# USB-CAN-Adapter.net
KiCad netlist of a schematic drawn in EAGLE
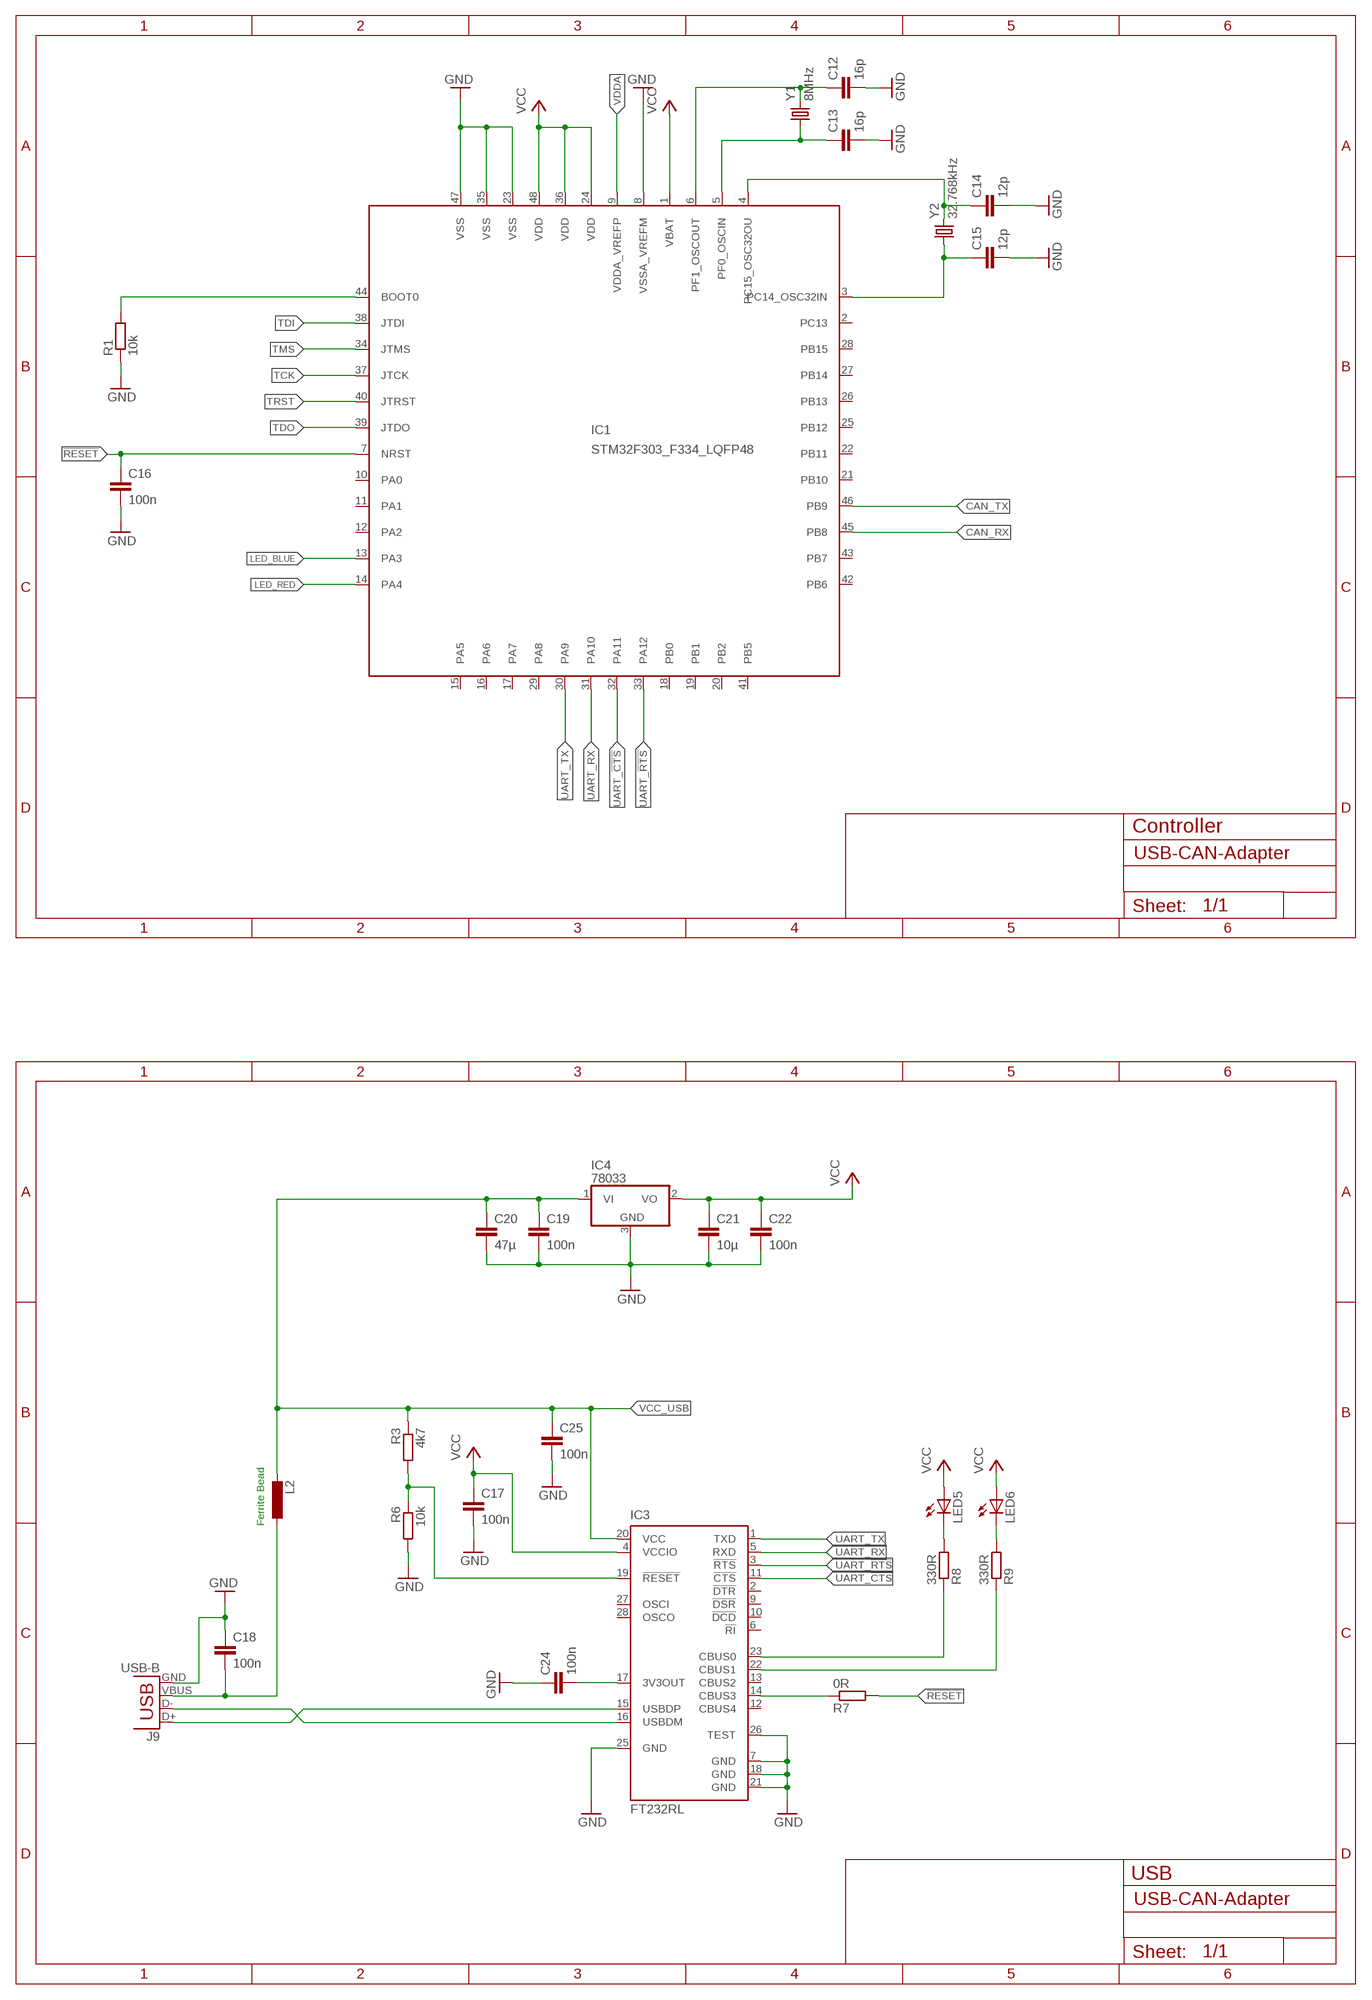
[diagram p0: schematic, sheet 1, part 1 of 2]
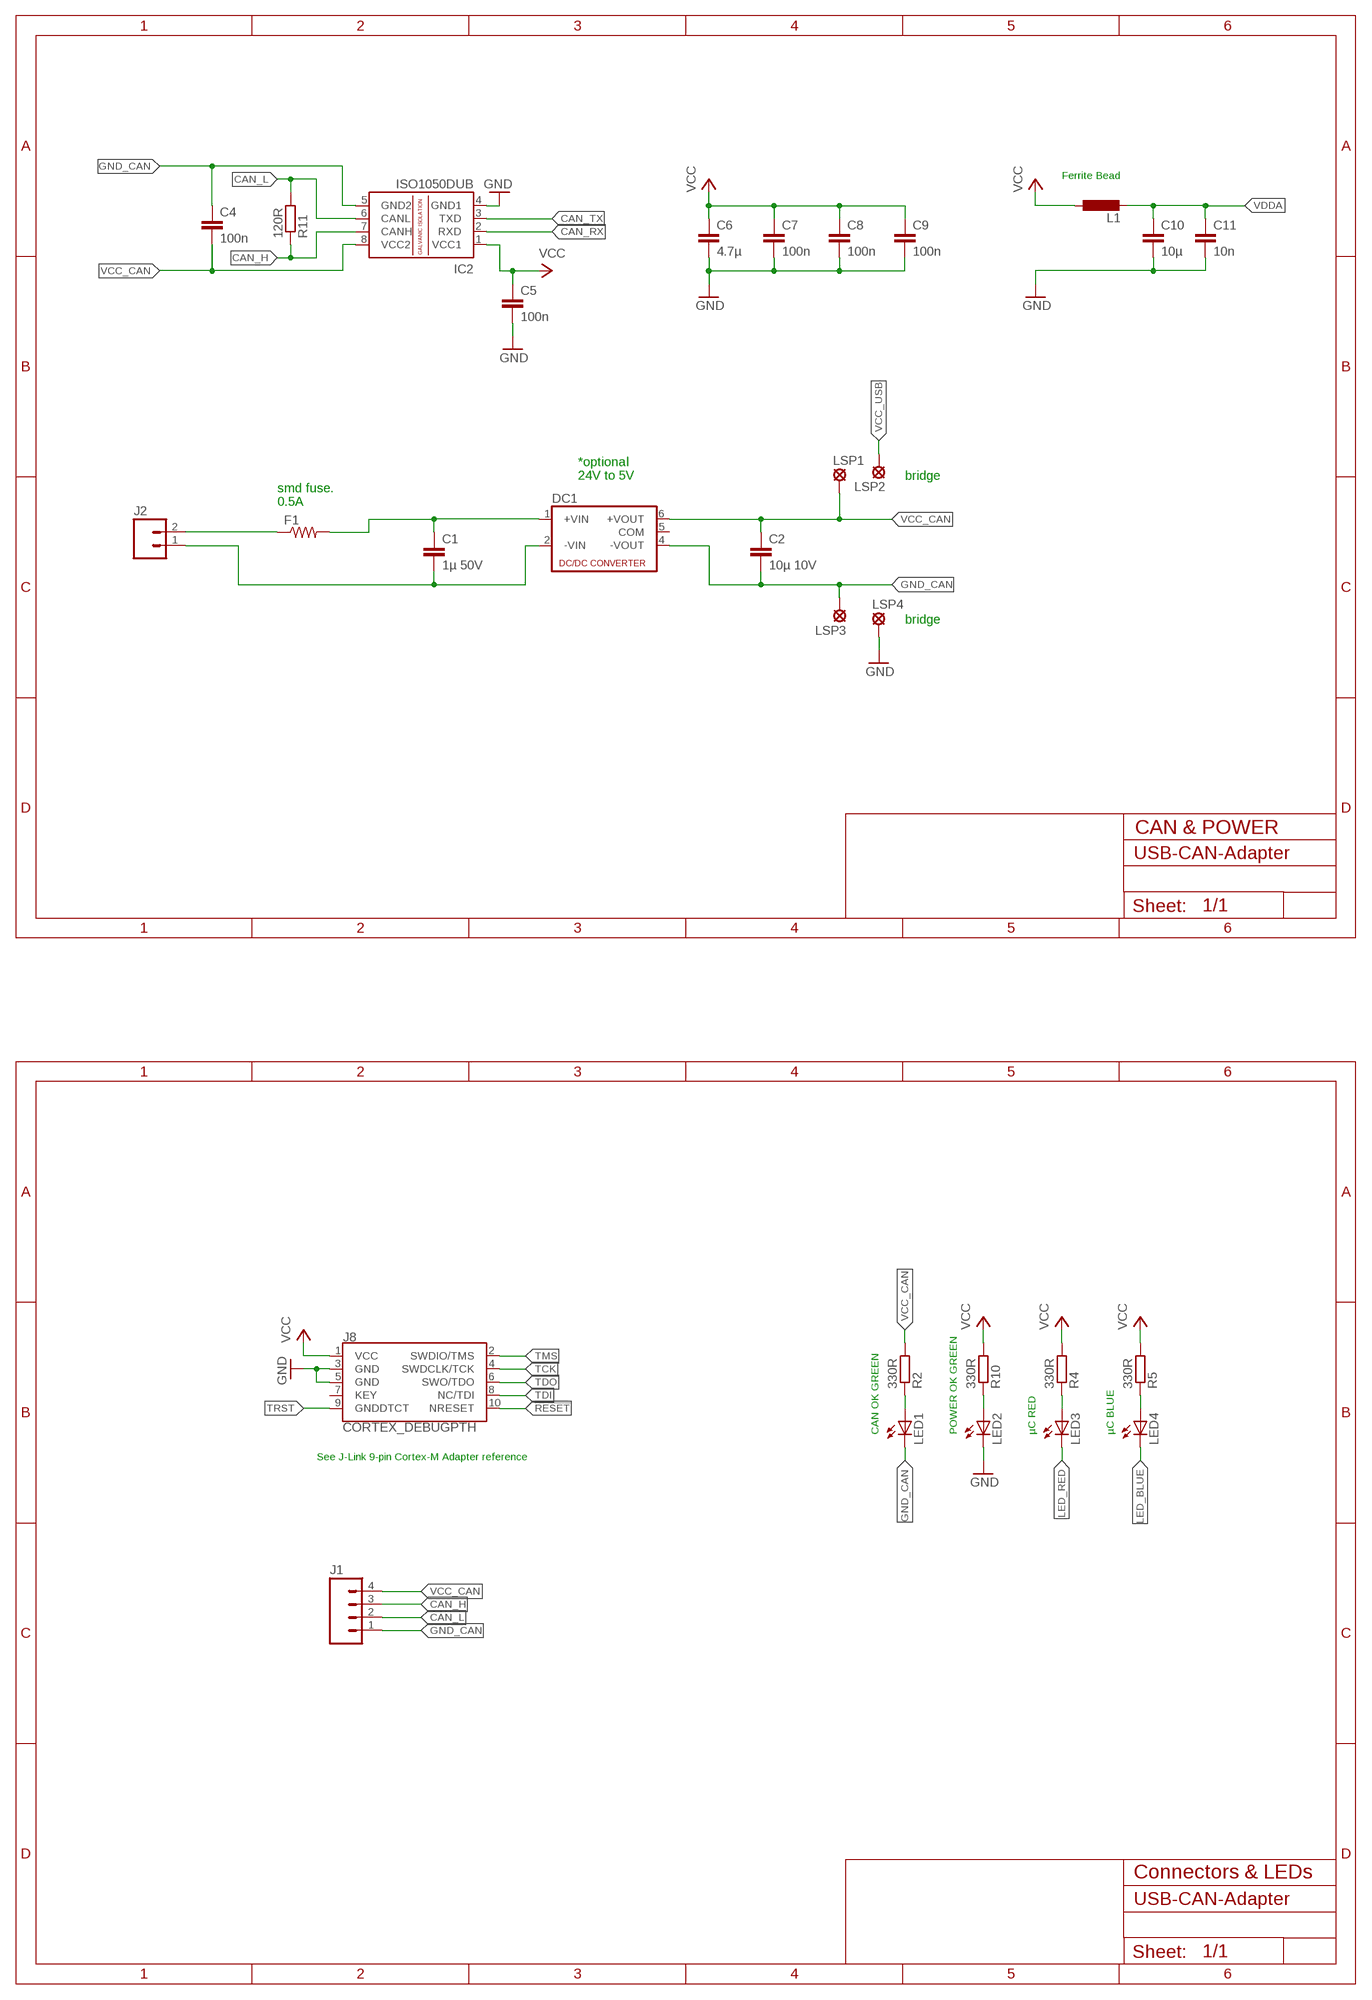
[diagram p1: schematic, sheet 1, part 2 of 2]

(export (version "E")
  (design (tool "Eeschema 10.0.6"))
  (components
    (comp (ref "C1")
      (value "1µ 50V")
      (footprint "eagle-import:C0805")
      (libsource (lib "eagle-import") (part "C-EUC0805"))
    )
    (comp (ref "C2")
      (value "10µ 10V")
      (footprint "eagle-import:C0805")
      (libsource (lib "eagle-import") (part "C-EUC0805"))
    )
    (comp (ref "C4")
      (value "100n")
      (footprint "eagle-import:C0805")
      (libsource (lib "eagle-import") (part "C-EUC0805"))
    )
    (comp (ref "C5")
      (value "100n")
      (footprint "eagle-import:C0805")
      (libsource (lib "eagle-import") (part "C-EUC0805"))
    )
    (comp (ref "C6")
      (value "4.7µ")
      (footprint "eagle-import:C0805")
      (libsource (lib "eagle-import") (part "C-EUC0805"))
    )
    (comp (ref "C7")
      (value "100n")
      (footprint "eagle-import:C0805")
      (libsource (lib "eagle-import") (part "C-EUC0805"))
    )
    (comp (ref "C8")
      (value "100n")
      (footprint "eagle-import:C0805")
      (libsource (lib "eagle-import") (part "C-EUC0805"))
    )
    (comp (ref "C9")
      (value "100n")
      (footprint "eagle-import:C0805")
      (libsource (lib "eagle-import") (part "C-EUC0805"))
    )
    (comp (ref "C10")
      (value "10µ")
      (footprint "eagle-import:C0805")
      (libsource (lib "eagle-import") (part "C-EUC0805"))
    )
    (comp (ref "C11")
      (value "10n")
      (footprint "eagle-import:C0805")
      (libsource (lib "eagle-import") (part "C-EUC0805"))
    )
    (comp (ref "C12")
      (value "16p")
      (footprint "eagle-import:C0805")
      (libsource (lib "eagle-import") (part "C-EUC0805"))
    )
    (comp (ref "C13")
      (value "16p")
      (footprint "eagle-import:C0805")
      (libsource (lib "eagle-import") (part "C-EUC0805"))
    )
    (comp (ref "C14")
      (value "12p")
      (footprint "eagle-import:C0805")
      (libsource (lib "eagle-import") (part "C-EUC0805"))
    )
    (comp (ref "C15")
      (value "12p")
      (footprint "eagle-import:C0805")
      (libsource (lib "eagle-import") (part "C-EUC0805"))
    )
    (comp (ref "C16")
      (value "100n")
      (footprint "eagle-import:C0805")
      (libsource (lib "eagle-import") (part "C-EUC0805"))
    )
    (comp (ref "C17")
      (value "100n")
      (footprint "eagle-import:C0805")
      (libsource (lib "eagle-import") (part "C-EUC0805"))
    )
    (comp (ref "C18")
      (value "100n")
      (footprint "eagle-import:C0805")
      (libsource (lib "eagle-import") (part "C-EUC0805"))
    )
    (comp (ref "C19")
      (value "100n")
      (footprint "eagle-import:C0805")
      (libsource (lib "eagle-import") (part "C-EUC0805"))
    )
    (comp (ref "C20")
      (value "47µ")
      (footprint "eagle-import:C0805")
      (libsource (lib "eagle-import") (part "C-EUC0805"))
    )
    (comp (ref "C21")
      (value "10µ")
      (footprint "eagle-import:C0805")
      (libsource (lib "eagle-import") (part "C-EUC0805"))
    )
    (comp (ref "C22")
      (value "100n")
      (footprint "eagle-import:C0805")
      (libsource (lib "eagle-import") (part "C-EUC0805"))
    )
    (comp (ref "C24")
      (value "100n")
      (footprint "eagle-import:C0805")
      (libsource (lib "eagle-import") (part "C-EUC0805"))
    )
    (comp (ref "C25")
      (value "100n")
      (footprint "eagle-import:C0805")
      (libsource (lib "eagle-import") (part "C-EUC0805"))
    )
    (comp (ref "DC1")
      (value "NMA")
      (footprint "eagle-import:NMA")
      (fields (field (name "MF") "C & D TECHNOLOGIES, INC") (field (name "MPN") "NMA0515SC"))
      (libsource (lib "eagle-import") (part "NMA"))
    )
    (comp (ref "F1")
      (value "R-US_R0805")
      (footprint "eagle-import:R0805")
      (libsource (lib "eagle-import") (part "R-US_R0805"))
    )
    (comp (ref "IC1")
      (value "STM32F303_F334_LQFP48")
      (footprint "eagle-import:LQFP48_PACKAGE")
      (libsource (lib "eagle-import") (part "STM32F303_F334_LQFP48"))
    )
    (comp (ref "IC2")
      (value "ISO1050DUB")
      (footprint "eagle-import:DUB-R-PDSO-G8")
      (fields (field (name "MPN") "ISO1050DUBR"))
      (libsource (lib "eagle-import") (part "ISO1050DUB"))
    )
    (comp (ref "IC3")
      (value "FT232RL")
      (footprint "eagle-import:SSOP28")
      (libsource (lib "eagle-import") (part "FT232RL"))
    )
    (comp (ref "IC4")
      (value "78033")
      (footprint "eagle-import:TO252")
      (libsource (lib "eagle-import") (part "78DT05"))
    )
    (comp (ref "J1")
      (value "M04SCREW")
      (footprint "eagle-import:SCREWTERMINAL-3.5MM-4")
      (libsource (lib "eagle-import") (part "M04SCREW"))
    )
    (comp (ref "J2")
      (value "M023.5MM")
      (footprint "eagle-import:SCREWTERMINAL-3.5MM-2")
      (libsource (lib "eagle-import") (part "M023.5MM"))
    )
    (comp (ref "J8")
      (value "CORTEX_DEBUGPTH")
      (footprint "eagle-import:2X5-PTH-1.27MM")
      (libsource (lib "eagle-import") (part "CORTEX_DEBUGPTH"))
    )
    (comp (ref "J9")
      (value "USB-B")
      (footprint "eagle-import:USB-B-PTH")
      (libsource (lib "eagle-import") (part "USBPTH"))
    )
    (comp (ref "L1")
      (value "L-EUL2012C")
      (footprint "eagle-import:L2012C")
      (libsource (lib "eagle-import") (part "L-EUL2012C"))
    )
    (comp (ref "L2")
      (value "L-EUL2012C")
      (footprint "eagle-import:L2012C")
      (libsource (lib "eagle-import") (part "L-EUL2012C"))
    )
    (comp (ref "LED1")
      (value "LEDCHIP-LED0805")
      (footprint "eagle-import:CHIP-LED0805")
      (libsource (lib "eagle-import") (part "LEDCHIP-LED0805"))
    )
    (comp (ref "LED2")
      (value "LEDCHIP-LED0805")
      (footprint "eagle-import:CHIP-LED0805")
      (libsource (lib "eagle-import") (part "LEDCHIP-LED0805"))
    )
    (comp (ref "LED3")
      (value "LEDCHIP-LED0805")
      (footprint "eagle-import:CHIP-LED0805")
      (libsource (lib "eagle-import") (part "LEDCHIP-LED0805"))
    )
    (comp (ref "LED4")
      (value "LEDCHIP-LED0805")
      (footprint "eagle-import:CHIP-LED0805")
      (libsource (lib "eagle-import") (part "LEDCHIP-LED0805"))
    )
    (comp (ref "LED5")
      (value "LEDCHIP-LED0805")
      (footprint "eagle-import:CHIP-LED0805")
      (libsource (lib "eagle-import") (part "LEDCHIP-LED0805"))
    )
    (comp (ref "LED6")
      (value "LEDCHIP-LED0805")
      (footprint "eagle-import:CHIP-LED0805")
      (libsource (lib "eagle-import") (part "LEDCHIP-LED0805"))
    )
    (comp (ref "LSP1")
      (value "LSP13")
      (footprint "eagle-import:LSP13")
      (libsource (lib "eagle-import") (part "LSP13"))
    )
    (comp (ref "LSP2")
      (value "LSP13")
      (footprint "eagle-import:LSP13")
      (libsource (lib "eagle-import") (part "LSP13"))
    )
    (comp (ref "LSP3")
      (value "LSP13")
      (footprint "eagle-import:LSP13")
      (libsource (lib "eagle-import") (part "LSP13"))
    )
    (comp (ref "LSP4")
      (value "LSP13")
      (footprint "eagle-import:LSP13")
      (libsource (lib "eagle-import") (part "LSP13"))
    )
    (comp (ref "R1")
      (value "10k")
      (footprint "eagle-import:R0805")
      (libsource (lib "eagle-import") (part "R-EU_R0805"))
    )
    (comp (ref "R2")
      (value "330R")
      (footprint "eagle-import:R0805")
      (libsource (lib "eagle-import") (part "R-EU_R0805"))
    )
    (comp (ref "R3")
      (value "4k7")
      (footprint "eagle-import:R0805")
      (libsource (lib "eagle-import") (part "R-EU_R0805"))
    )
    (comp (ref "R4")
      (value "330R")
      (footprint "eagle-import:R0805")
      (libsource (lib "eagle-import") (part "R-EU_R0805"))
    )
    (comp (ref "R5")
      (value "330R")
      (footprint "eagle-import:R0805")
      (libsource (lib "eagle-import") (part "R-EU_R0805"))
    )
    (comp (ref "R6")
      (value "10k")
      (footprint "eagle-import:R0805")
      (libsource (lib "eagle-import") (part "R-EU_R0805"))
    )
    (comp (ref "R7")
      (value "0R")
      (footprint "eagle-import:R0805")
      (libsource (lib "eagle-import") (part "R-EU_R0805"))
    )
    (comp (ref "R8")
      (value "330R")
      (footprint "eagle-import:R0805")
      (libsource (lib "eagle-import") (part "R-EU_R0805"))
    )
    (comp (ref "R9")
      (value "330R")
      (footprint "eagle-import:R0805")
      (libsource (lib "eagle-import") (part "R-EU_R0805"))
    )
    (comp (ref "R10")
      (value "330R")
      (footprint "eagle-import:R0805")
      (libsource (lib "eagle-import") (part "R-EU_R0805"))
    )
    (comp (ref "R11")
      (value "120R")
      (footprint "eagle-import:R0805")
      (libsource (lib "eagle-import") (part "R-EU_R0805"))
    )
    (comp (ref "Y1")
      (value "8MHz")
      (footprint "eagle-import:CRYSTAL-SMD-5X3")
      (libsource (lib "eagle-import") (part "CRYSTALCRYSTAL-SMD-5X3-12.288MHZ"))
    )
    (comp (ref "Y2")
      (value "32.768kHz")
      (footprint "eagle-import:CRYSTAL-SMD-3.2X1.5MM")
      (libsource (lib "eagle-import") (part "CRYSTAL3.2X1.5MM"))
    )
  )
  (nets
    (net (code "1") (name "/UART_~{CTS}") (class "Default")
      (node (ref "IC1") (pin "32") (pinfunction "PA11_32") (pintype "bidirectional"))
      (node (ref "IC3") (pin "11") (pinfunction "~{CTS}_11") (pintype "input"))
    )
    (net (code "2") (name "/UART_~{RTS}") (class "Default")
      (node (ref "IC1") (pin "33") (pinfunction "PA12_33") (pintype "bidirectional"))
      (node (ref "IC3") (pin "3") (pinfunction "~{RTS}_3") (pintype "output"))
    )
    (net (code "3") (name "/~{RESET}") (class "Default")
      (node (ref "C16") (pin "1") (pinfunction "1_1") (pintype "passive"))
      (node (ref "IC1") (pin "7") (pinfunction "NRST_7") (pintype "input"))
      (node (ref "J8") (pin "10") (pinfunction "NRESET_10") (pintype "bidirectional"))
      (node (ref "R7") (pin "2") (pinfunction "2_2") (pintype "passive"))
    )
    (net (code "4") (name "CAN_H") (class "Default")
      (node (ref "IC2") (pin "7") (pinfunction "CANH_7") (pintype "input"))
      (node (ref "J1") (pin "3") (pinfunction "3_3") (pintype "passive"))
      (node (ref "R11") (pin "1") (pinfunction "1_1") (pintype "passive"))
    )
    (net (code "5") (name "CAN_L") (class "Default")
      (node (ref "IC2") (pin "6") (pinfunction "CANL_6") (pintype "input"))
      (node (ref "J1") (pin "2") (pinfunction "2_2") (pintype "passive"))
      (node (ref "R11") (pin "2") (pinfunction "2_2") (pintype "passive"))
    )
    (net (code "6") (name "CAN_RX") (class "Default")
      (node (ref "IC1") (pin "45") (pinfunction "PB8_45") (pintype "bidirectional"))
      (node (ref "IC2") (pin "2") (pinfunction "RXD_2") (pintype "input"))
    )
    (net (code "7") (name "CAN_TX") (class "Default")
      (node (ref "IC1") (pin "46") (pinfunction "PB9_46") (pintype "bidirectional"))
      (node (ref "IC2") (pin "3") (pinfunction "TXD_3") (pintype "input"))
    )
    (net (code "8") (name "GND") (class "Default")
      (node (ref "C10") (pin "2") (pinfunction "2_2") (pintype "passive"))
      (node (ref "C11") (pin "2") (pinfunction "2_2") (pintype "passive"))
      (node (ref "C12") (pin "2") (pinfunction "2_2") (pintype "passive"))
      (node (ref "C13") (pin "2") (pinfunction "2_2") (pintype "passive"))
      (node (ref "C14") (pin "2") (pinfunction "2_2") (pintype "passive"))
      (node (ref "C15") (pin "2") (pinfunction "2_2") (pintype "passive"))
      (node (ref "C16") (pin "2") (pinfunction "2_2") (pintype "passive"))
      (node (ref "C17") (pin "2") (pinfunction "2_2") (pintype "passive"))
      (node (ref "C18") (pin "1") (pinfunction "1_1") (pintype "passive"))
      (node (ref "C19") (pin "2") (pinfunction "2_2") (pintype "passive"))
      (node (ref "C20") (pin "2") (pinfunction "2_2") (pintype "passive"))
      (node (ref "C21") (pin "2") (pinfunction "2_2") (pintype "passive"))
      (node (ref "C22") (pin "2") (pinfunction "2_2") (pintype "passive"))
      (node (ref "C24") (pin "1") (pinfunction "1_1") (pintype "passive"))
      (node (ref "C25") (pin "2") (pinfunction "2_2") (pintype "passive"))
      (node (ref "C5") (pin "2") (pinfunction "2_2") (pintype "passive"))
      (node (ref "C6") (pin "2") (pinfunction "2_2") (pintype "passive"))
      (node (ref "C7") (pin "2") (pinfunction "2_2") (pintype "passive"))
      (node (ref "C8") (pin "2") (pinfunction "2_2") (pintype "passive"))
      (node (ref "C9") (pin "2") (pinfunction "2_2") (pintype "passive"))
      (node (ref "IC1") (pin "23") (pinfunction "VSS_23") (pintype "power_in"))
      (node (ref "IC1") (pin "35") (pinfunction "VSS_35") (pintype "power_in"))
      (node (ref "IC1") (pin "47") (pinfunction "VSS_47") (pintype "power_in"))
      (node (ref "IC1") (pin "8") (pinfunction "VSSA_VREFM_8") (pintype "power_in"))
      (node (ref "IC2") (pin "4") (pinfunction "GND1_4") (pintype "input"))
      (node (ref "IC3") (pin "18") (pinfunction "GND_18") (pintype "power_in"))
      (node (ref "IC3") (pin "21") (pinfunction "GND_21") (pintype "power_in"))
      (node (ref "IC3") (pin "25") (pinfunction "GND_25") (pintype "power_in"))
      (node (ref "IC3") (pin "26") (pinfunction "TEST_26") (pintype "input"))
      (node (ref "IC3") (pin "7") (pinfunction "GND_7") (pintype "power_in"))
      (node (ref "IC4") (pin "3") (pinfunction "GND_3") (pintype "passive"))
      (node (ref "J8") (pin "3") (pinfunction "GND_3") (pintype "bidirectional"))
      (node (ref "J8") (pin "5") (pinfunction "GND_5") (pintype "bidirectional"))
      (node (ref "J9") (pin "GND") (pinfunction "GND_GND") (pintype "bidirectional"))
      (node (ref "LED2") (pin "C") (pinfunction "C_C") (pintype "passive"))
      (node (ref "LSP4") (pin "MP") (pinfunction "MP_MP") (pintype "passive"))
      (node (ref "R1") (pin "1") (pinfunction "1_1") (pintype "passive"))
      (node (ref "R6") (pin "2") (pinfunction "2_2") (pintype "passive"))
    )
    (net (code "9") (name "GND_CAN") (class "Default")
      (node (ref "C2") (pin "2") (pinfunction "2_2") (pintype "passive"))
      (node (ref "C4") (pin "1") (pinfunction "1_1") (pintype "passive"))
      (node (ref "DC1") (pin "4") (pinfunction "-VOUT_4") (pintype "passive"))
      (node (ref "IC2") (pin "5") (pinfunction "GND2_5") (pintype "input"))
      (node (ref "J1") (pin "1") (pinfunction "1_1") (pintype "passive"))
      (node (ref "LED1") (pin "C") (pinfunction "C_C") (pintype "passive"))
      (node (ref "LSP3") (pin "MP") (pinfunction "MP_MP") (pintype "passive"))
    )
    (net (code "10") (name "LED_BLUE") (class "Default")
      (node (ref "IC1") (pin "13") (pinfunction "PA3_13") (pintype "bidirectional"))
      (node (ref "LED4") (pin "C") (pinfunction "C_C") (pintype "passive"))
    )
    (net (code "11") (name "LED_RED") (class "Default")
      (node (ref "IC1") (pin "14") (pinfunction "PA4_14") (pintype "bidirectional"))
      (node (ref "LED3") (pin "C") (pinfunction "C_C") (pintype "passive"))
    )
    (net (code "12") (name "Net-(C18-Pad2)") (class "Default")
      (node (ref "C18") (pin "2") (pinfunction "2_2") (pintype "passive"))
      (node (ref "J9") (pin "VBUS") (pinfunction "VBUS_VBUS") (pintype "bidirectional"))
      (node (ref "L2") (pin "1") (pinfunction "1_1") (pintype "passive"))
    )
    (net (code "13") (name "Net-(DC1-+VIN)") (class "Default")
      (node (ref "C1") (pin "1") (pinfunction "1_1") (pintype "passive"))
      (node (ref "DC1") (pin "1") (pinfunction "+VIN_1") (pintype "passive"))
      (node (ref "F1") (pin "2") (pinfunction "2_2") (pintype "passive"))
    )
    (net (code "14") (name "Net-(DC1--VIN)") (class "Default")
      (node (ref "C1") (pin "2") (pinfunction "2_2") (pintype "passive"))
      (node (ref "DC1") (pin "2") (pinfunction "-VIN_2") (pintype "passive"))
      (node (ref "J2") (pin "1") (pinfunction "1_1") (pintype "passive"))
    )
    (net (code "15") (name "Net-(F1-Pad1)") (class "Default")
      (node (ref "F1") (pin "1") (pinfunction "1_1") (pintype "passive"))
      (node (ref "J2") (pin "2") (pinfunction "2_2") (pintype "passive"))
    )
    (net (code "16") (name "Net-(IC1-BOOT0)") (class "Default")
      (node (ref "IC1") (pin "44") (pinfunction "BOOT0_44") (pintype "input"))
      (node (ref "R1") (pin "2") (pinfunction "2_2") (pintype "passive"))
    )
    (net (code "17") (name "Net-(IC1-PC14_OSC32IN)") (class "Default")
      (node (ref "C15") (pin "1") (pinfunction "1_1") (pintype "passive"))
      (node (ref "IC1") (pin "3") (pinfunction "PC14_OSC32IN_3") (pintype "bidirectional"))
      (node (ref "Y2") (pin "P$1") (pinfunction "1_P$1") (pintype "passive"))
    )
    (net (code "18") (name "Net-(IC1-PC15_OSC32OU)") (class "Default")
      (node (ref "C14") (pin "1") (pinfunction "1_1") (pintype "passive"))
      (node (ref "IC1") (pin "4") (pinfunction "PC15_OSC32OU_4") (pintype "bidirectional"))
      (node (ref "Y2") (pin "P$2") (pinfunction "2_P$2") (pintype "passive"))
    )
    (net (code "19") (name "Net-(IC1-PF0_OSCIN)") (class "Default")
      (node (ref "C13") (pin "1") (pinfunction "1_1") (pintype "passive"))
      (node (ref "IC1") (pin "5") (pinfunction "PF0_OSCIN_5") (pintype "bidirectional"))
      (node (ref "Y1") (pin "1") (pinfunction "1_1") (pintype "passive"))
    )
    (net (code "20") (name "Net-(IC1-PF1_OSCOUT)") (class "Default")
      (node (ref "C12") (pin "1") (pinfunction "1_1") (pintype "passive"))
      (node (ref "IC1") (pin "6") (pinfunction "PF1_OSCOUT_6") (pintype "bidirectional"))
      (node (ref "Y1") (pin "3") (pinfunction "2_3") (pintype "passive"))
    )
    (net (code "21") (name "Net-(IC3-3V3OUT)") (class "Default")
      (node (ref "C24") (pin "2") (pinfunction "2_2") (pintype "passive"))
      (node (ref "IC3") (pin "17") (pinfunction "3V3OUT_17") (pintype "output"))
    )
    (net (code "22") (name "Net-(IC3-CBUS0)") (class "Default")
      (node (ref "IC3") (pin "23") (pinfunction "CBUS0_23") (pintype "bidirectional"))
      (node (ref "R8") (pin "1") (pinfunction "1_1") (pintype "passive"))
    )
    (net (code "23") (name "Net-(IC3-CBUS1)") (class "Default")
      (node (ref "IC3") (pin "22") (pinfunction "CBUS1_22") (pintype "bidirectional"))
      (node (ref "R9") (pin "1") (pinfunction "1_1") (pintype "passive"))
    )
    (net (code "24") (name "Net-(IC3-CBUS3)") (class "Default")
      (node (ref "IC3") (pin "14") (pinfunction "CBUS3_14") (pintype "bidirectional"))
      (node (ref "R7") (pin "1") (pinfunction "1_1") (pintype "passive"))
    )
    (net (code "25") (name "Net-(IC3-USBDM)") (class "Default")
      (node (ref "IC3") (pin "16") (pinfunction "USBDM_16") (pintype "bidirectional"))
      (node (ref "J9") (pin "D-") (pinfunction "D-_D-") (pintype "bidirectional"))
    )
    (net (code "26") (name "Net-(IC3-USBDP)") (class "Default")
      (node (ref "IC3") (pin "15") (pinfunction "USBDP_15") (pintype "bidirectional"))
      (node (ref "J9") (pin "D+") (pinfunction "D+_D+") (pintype "bidirectional"))
    )
    (net (code "27") (name "Net-(IC3-~{RESET})") (class "Default")
      (node (ref "IC3") (pin "19") (pinfunction "~{RESET}_19") (pintype "input"))
      (node (ref "R3") (pin "2") (pinfunction "2_2") (pintype "passive"))
      (node (ref "R6") (pin "1") (pinfunction "1_1") (pintype "passive"))
    )
    (net (code "28") (name "Net-(LED1-PadA)") (class "Default")
      (node (ref "LED1") (pin "A") (pinfunction "A_A") (pintype "passive"))
      (node (ref "R2") (pin "1") (pinfunction "1_1") (pintype "passive"))
    )
    (net (code "29") (name "Net-(LED2-PadA)") (class "Default")
      (node (ref "LED2") (pin "A") (pinfunction "A_A") (pintype "passive"))
      (node (ref "R10") (pin "1") (pinfunction "1_1") (pintype "passive"))
    )
    (net (code "30") (name "Net-(LED3-PadA)") (class "Default")
      (node (ref "LED3") (pin "A") (pinfunction "A_A") (pintype "passive"))
      (node (ref "R4") (pin "1") (pinfunction "1_1") (pintype "passive"))
    )
    (net (code "31") (name "Net-(LED4-PadA)") (class "Default")
      (node (ref "LED4") (pin "A") (pinfunction "A_A") (pintype "passive"))
      (node (ref "R5") (pin "1") (pinfunction "1_1") (pintype "passive"))
    )
    (net (code "32") (name "Net-(LED5-PadC)") (class "Default")
      (node (ref "LED5") (pin "C") (pinfunction "C_C") (pintype "passive"))
      (node (ref "R8") (pin "2") (pinfunction "2_2") (pintype "passive"))
    )
    (net (code "33") (name "Net-(LED6-PadC)") (class "Default")
      (node (ref "LED6") (pin "C") (pinfunction "C_C") (pintype "passive"))
      (node (ref "R9") (pin "2") (pinfunction "2_2") (pintype "passive"))
    )
    (net (code "34") (name "TCK") (class "Default")
      (node (ref "IC1") (pin "37") (pinfunction "JTCK_37") (pintype "input"))
      (node (ref "J8") (pin "4") (pinfunction "SWDCLK/TCK_4") (pintype "bidirectional"))
    )
    (net (code "35") (name "TDI") (class "Default")
      (node (ref "IC1") (pin "38") (pinfunction "JTDI_38") (pintype "input"))
      (node (ref "J8") (pin "8") (pinfunction "NC/TDI_8") (pintype "bidirectional"))
    )
    (net (code "36") (name "TDO") (class "Default")
      (node (ref "IC1") (pin "39") (pinfunction "JTDO_39") (pintype "output"))
      (node (ref "J8") (pin "6") (pinfunction "SWO/TDO_6") (pintype "bidirectional"))
    )
    (net (code "37") (name "TMS") (class "Default")
      (node (ref "IC1") (pin "34") (pinfunction "JTMS_34") (pintype "input"))
      (node (ref "J8") (pin "2") (pinfunction "SWDIO/TMS_2") (pintype "bidirectional"))
    )
    (net (code "38") (name "TRST") (class "Default")
      (node (ref "IC1") (pin "40") (pinfunction "JTRST_40") (pintype "input"))
      (node (ref "J8") (pin "9") (pinfunction "GNDDTCT_9") (pintype "bidirectional"))
    )
    (net (code "39") (name "UART_RX") (class "Default")
      (node (ref "IC1") (pin "31") (pinfunction "PA10_31") (pintype "bidirectional"))
      (node (ref "IC3") (pin "5") (pinfunction "RXD_5") (pintype "input"))
    )
    (net (code "40") (name "UART_TX") (class "Default")
      (node (ref "IC1") (pin "30") (pinfunction "PA9_30") (pintype "bidirectional"))
      (node (ref "IC3") (pin "1") (pinfunction "TXD_1") (pintype "output"))
    )
    (net (code "41") (name "VCC") (class "Default")
      (node (ref "C17") (pin "1") (pinfunction "1_1") (pintype "passive"))
      (node (ref "C21") (pin "1") (pinfunction "1_1") (pintype "passive"))
      (node (ref "C22") (pin "1") (pinfunction "1_1") (pintype "passive"))
      (node (ref "C5") (pin "1") (pinfunction "1_1") (pintype "passive"))
      (node (ref "C6") (pin "1") (pinfunction "1_1") (pintype "passive"))
      (node (ref "C7") (pin "1") (pinfunction "1_1") (pintype "passive"))
      (node (ref "C8") (pin "1") (pinfunction "1_1") (pintype "passive"))
      (node (ref "C9") (pin "1") (pinfunction "1_1") (pintype "passive"))
      (node (ref "IC1") (pin "1") (pinfunction "VBAT_1") (pintype "passive"))
      (node (ref "IC1") (pin "24") (pinfunction "VDD_24") (pintype "power_in"))
      (node (ref "IC1") (pin "36") (pinfunction "VDD_36") (pintype "power_in"))
      (node (ref "IC1") (pin "48") (pinfunction "VDD_48") (pintype "power_in"))
      (node (ref "IC2") (pin "1") (pinfunction "VCC1_1") (pintype "input"))
      (node (ref "IC3") (pin "4") (pinfunction "VCCIO_4") (pintype "power_in"))
      (node (ref "IC4") (pin "2") (pinfunction "VO_2") (pintype "passive"))
      (node (ref "J8") (pin "1") (pinfunction "VCC_1") (pintype "bidirectional"))
      (node (ref "L1") (pin "1") (pinfunction "1_1") (pintype "passive"))
      (node (ref "LED5") (pin "A") (pinfunction "A_A") (pintype "passive"))
      (node (ref "LED6") (pin "A") (pinfunction "A_A") (pintype "passive"))
      (node (ref "R10") (pin "2") (pinfunction "2_2") (pintype "passive"))
      (node (ref "R4") (pin "2") (pinfunction "2_2") (pintype "passive"))
      (node (ref "R5") (pin "2") (pinfunction "2_2") (pintype "passive"))
    )
    (net (code "42") (name "VCC_CAN") (class "Default")
      (node (ref "C2") (pin "1") (pinfunction "1_1") (pintype "passive"))
      (node (ref "C4") (pin "2") (pinfunction "2_2") (pintype "passive"))
      (node (ref "DC1") (pin "6") (pinfunction "+VOUT_6") (pintype "passive"))
      (node (ref "IC2") (pin "8") (pinfunction "VCC2_8") (pintype "input"))
      (node (ref "J1") (pin "4") (pinfunction "4_4") (pintype "passive"))
      (node (ref "LSP1") (pin "MP") (pinfunction "MP_MP") (pintype "passive"))
      (node (ref "R2") (pin "2") (pinfunction "2_2") (pintype "passive"))
    )
    (net (code "43") (name "VCC_USB") (class "Default")
      (node (ref "C19") (pin "1") (pinfunction "1_1") (pintype "passive"))
      (node (ref "C20") (pin "1") (pinfunction "1_1") (pintype "passive"))
      (node (ref "C25") (pin "1") (pinfunction "1_1") (pintype "passive"))
      (node (ref "IC3") (pin "20") (pinfunction "VCC_20") (pintype "power_in"))
      (node (ref "IC4") (pin "1") (pinfunction "VI_1") (pintype "input"))
      (node (ref "L2") (pin "2") (pinfunction "2_2") (pintype "passive"))
      (node (ref "LSP2") (pin "MP") (pinfunction "MP_MP") (pintype "passive"))
      (node (ref "R3") (pin "1") (pinfunction "1_1") (pintype "passive"))
    )
    (net (code "44") (name "VDDA") (class "Default")
      (node (ref "C10") (pin "1") (pinfunction "1_1") (pintype "passive"))
      (node (ref "C11") (pin "1") (pinfunction "1_1") (pintype "passive"))
      (node (ref "IC1") (pin "9") (pinfunction "VDDA_VREFP_9") (pintype "power_in"))
      (node (ref "L1") (pin "2") (pinfunction "2_2") (pintype "passive"))
    )
    (net (code "45") (name "unconnected-(DC1-COM-Pad5)") (class "Default")
      (node (ref "DC1") (pin "5") (pinfunction "COM_5") (pintype "passive"))
    )
    (net (code "46") (name "unconnected-(IC1-PA0-Pad10)") (class "Default")
      (node (ref "IC1") (pin "10") (pinfunction "PA0_10") (pintype "bidirectional"))
    )
    (net (code "47") (name "unconnected-(IC1-PA1-Pad11)") (class "Default")
      (node (ref "IC1") (pin "11") (pinfunction "PA1_11") (pintype "bidirectional"))
    )
    (net (code "48") (name "unconnected-(IC1-PA2-Pad12)") (class "Default")
      (node (ref "IC1") (pin "12") (pinfunction "PA2_12") (pintype "bidirectional"))
    )
    (net (code "49") (name "unconnected-(IC1-PA5-Pad15)") (class "Default")
      (node (ref "IC1") (pin "15") (pinfunction "PA5_15") (pintype "bidirectional"))
    )
    (net (code "50") (name "unconnected-(IC1-PA6-Pad16)") (class "Default")
      (node (ref "IC1") (pin "16") (pinfunction "PA6_16") (pintype "bidirectional"))
    )
    (net (code "51") (name "unconnected-(IC1-PA7-Pad17)") (class "Default")
      (node (ref "IC1") (pin "17") (pinfunction "PA7_17") (pintype "bidirectional"))
    )
    (net (code "52") (name "unconnected-(IC1-PA8-Pad29)") (class "Default")
      (node (ref "IC1") (pin "29") (pinfunction "PA8_29") (pintype "bidirectional"))
    )
    (net (code "53") (name "unconnected-(IC1-PB0-Pad18)") (class "Default")
      (node (ref "IC1") (pin "18") (pinfunction "PB0_18") (pintype "bidirectional"))
    )
    (net (code "54") (name "unconnected-(IC1-PB1-Pad19)") (class "Default")
      (node (ref "IC1") (pin "19") (pinfunction "PB1_19") (pintype "bidirectional"))
    )
    (net (code "55") (name "unconnected-(IC1-PB2-Pad20)") (class "Default")
      (node (ref "IC1") (pin "20") (pinfunction "PB2_20") (pintype "bidirectional"))
    )
    (net (code "56") (name "unconnected-(IC1-PB5-Pad41)") (class "Default")
      (node (ref "IC1") (pin "41") (pinfunction "PB5_41") (pintype "bidirectional"))
    )
    (net (code "57") (name "unconnected-(IC1-PB6-Pad42)") (class "Default")
      (node (ref "IC1") (pin "42") (pinfunction "PB6_42") (pintype "bidirectional"))
    )
    (net (code "58") (name "unconnected-(IC1-PB7-Pad43)") (class "Default")
      (node (ref "IC1") (pin "43") (pinfunction "PB7_43") (pintype "bidirectional"))
    )
    (net (code "59") (name "unconnected-(IC1-PB10-Pad21)") (class "Default")
      (node (ref "IC1") (pin "21") (pinfunction "PB10_21") (pintype "bidirectional"))
    )
    (net (code "60") (name "unconnected-(IC1-PB11-Pad22)") (class "Default")
      (node (ref "IC1") (pin "22") (pinfunction "PB11_22") (pintype "bidirectional"))
    )
    (net (code "61") (name "unconnected-(IC1-PB12-Pad25)") (class "Default")
      (node (ref "IC1") (pin "25") (pinfunction "PB12_25") (pintype "bidirectional"))
    )
    (net (code "62") (name "unconnected-(IC1-PB13-Pad26)") (class "Default")
      (node (ref "IC1") (pin "26") (pinfunction "PB13_26") (pintype "bidirectional"))
    )
    (net (code "63") (name "unconnected-(IC1-PB14-Pad27)") (class "Default")
      (node (ref "IC1") (pin "27") (pinfunction "PB14_27") (pintype "bidirectional"))
    )
    (net (code "64") (name "unconnected-(IC1-PB15-Pad28)") (class "Default")
      (node (ref "IC1") (pin "28") (pinfunction "PB15_28") (pintype "bidirectional"))
    )
    (net (code "65") (name "unconnected-(IC1-PC13-Pad2)") (class "Default")
      (node (ref "IC1") (pin "2") (pinfunction "PC13_2") (pintype "bidirectional"))
    )
    (net (code "66") (name "unconnected-(IC3-CBUS2-Pad13)") (class "Default")
      (node (ref "IC3") (pin "13") (pinfunction "CBUS2_13") (pintype "bidirectional"))
    )
    (net (code "67") (name "unconnected-(IC3-CBUS4-Pad12)") (class "Default")
      (node (ref "IC3") (pin "12") (pinfunction "CBUS4_12") (pintype "bidirectional"))
    )
    (net (code "68") (name "unconnected-(IC3-OSCI-Pad27)") (class "Default")
      (node (ref "IC3") (pin "27") (pinfunction "OSCI_27") (pintype "input"))
    )
    (net (code "69") (name "unconnected-(IC3-OSCO-Pad28)") (class "Default")
      (node (ref "IC3") (pin "28") (pinfunction "OSCO_28") (pintype "output"))
    )
    (net (code "70") (name "unconnected-(IC3-~{DCD}-Pad10)") (class "Default")
      (node (ref "IC3") (pin "10") (pinfunction "~{DCD}_10") (pintype "input"))
    )
    (net (code "71") (name "unconnected-(IC3-~{DSR}-Pad9)") (class "Default")
      (node (ref "IC3") (pin "9") (pinfunction "~{DSR}_9") (pintype "input"))
    )
    (net (code "72") (name "unconnected-(IC3-~{DTR}-Pad2)") (class "Default")
      (node (ref "IC3") (pin "2") (pinfunction "~{DTR}_2") (pintype "output"))
    )
    (net (code "73") (name "unconnected-(IC3-~{RI}-Pad6)") (class "Default")
      (node (ref "IC3") (pin "6") (pinfunction "~{RI}_6") (pintype "input"))
    )
    (net (code "74") (name "unconnected-(J8-KEY-Pad7)") (class "Default")
      (node (ref "J8") (pin "7") (pinfunction "KEY_7") (pintype "bidirectional"))
    )
  )
)
